# Sheet1.net
KiCad netlist of a schematic drawn in Altium Designer
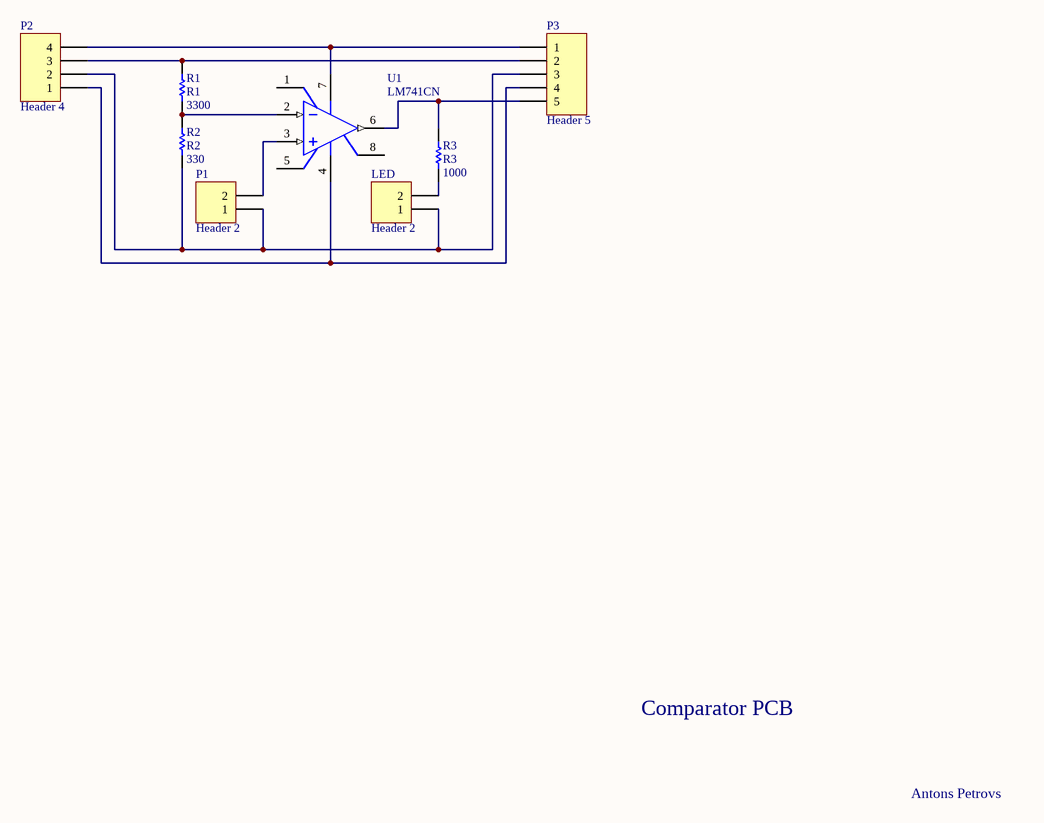
[diagram p0: Sheet1.SchDoc]

(export (version "E")
  (design (tool "Eeschema 10.0.6"))
  (components
    (comp (ref "LED")
      (value "Header 2")
      (footprint "HDR1X2")
      (description "Header, 2-Pin")
      (fields (field (name "PUBLISHER") "Altium Limited"))
      (libsource (lib "Miscellaneous Connectors") (part "Header 2"))
    )
    (comp (ref "P1")
      (value "Header 2")
      (footprint "HDR1X2")
      (description "Header, 2-Pin")
      (fields (field (name "PUBLISHER") "Altium Limited"))
      (libsource (lib "Miscellaneous Connectors") (part "Header 2"))
    )
    (comp (ref "P2")
      (value "Header 4")
      (footprint "HDR1X4")
      (description "Header, 4-Pin")
      (fields (field (name "PUBLISHER") "Altium Limited"))
      (libsource (lib "Miscellaneous Connectors") (part "Header 4"))
    )
    (comp (ref "P3")
      (value "Header 5")
      (footprint "HDR1X5")
      (description "Header, 5-Pin")
      (fields (field (name "PUBLISHER") "Altium Limited"))
      (libsource (lib "Miscellaneous Connectors") (part "Header 5"))
    )
    (comp (ref "R1")
      (value "R1")
      (footprint "AXIAL-0.3")
      (description "Resistor")
      (fields (field (name "ALTIUM_VALUE") "3300") (field (name "PUBLISHER") "Altium Limited"))
      (libsource (lib "Miscellaneous Devices") (part "Res1"))
    )
    (comp (ref "R2")
      (value "R2")
      (footprint "AXIAL-0.3")
      (description "Resistor")
      (fields (field (name "ALTIUM_VALUE") "330") (field (name "PUBLISHER") "Altium Limited"))
      (libsource (lib "Miscellaneous Devices") (part "Res1"))
    )
    (comp (ref "R3")
      (value "R3")
      (footprint "AXIAL-0.3")
      (description "Resistor")
      (fields (field (name "ALTIUM_VALUE") "1000") (field (name "PUBLISHER") "Altium Limited"))
      (libsource (lib "Miscellaneous Devices") (part "Res1"))
    )
    (comp (ref "U1")
      (value "LM741CN")
      (footprint "N08E")
      (description "Operational Amplifier, 8-pin MDIP")
      (fields
        (field (name "MANUFACTURER") "National Semiconductor")
        (field (name "PUBLISHER") "Altium Limited")
      )
      (libsource (lib "NSC Amplifier") (part "LM741CN"))
    )
  )
  (nets
    (net (code "1") (name "Net-(LED-Pad1)") (class "Default")
      (node (ref "LED") (pin "1") (pinfunction "1_1") (pintype "passive"))
      (node (ref "P1") (pin "1") (pinfunction "1_1") (pintype "passive"))
      (node (ref "P2") (pin "2") (pinfunction "2_2") (pintype "passive"))
      (node (ref "P3") (pin "3") (pinfunction "3_3") (pintype "passive"))
      (node (ref "R2") (pin "1") (pinfunction "1_1") (pintype "passive"))
    )
    (net (code "2") (name "Net-(LED-Pad2)") (class "Default")
      (node (ref "LED") (pin "2") (pinfunction "2_2") (pintype "passive"))
      (node (ref "R3") (pin "1") (pinfunction "1_1") (pintype "passive"))
    )
    (net (code "3") (name "Net-(P2-Pad3)") (class "Default")
      (node (ref "P2") (pin "3") (pinfunction "3_3") (pintype "passive"))
      (node (ref "P3") (pin "2") (pinfunction "2_2") (pintype "passive"))
      (node (ref "R1") (pin "2") (pinfunction "2_2") (pintype "passive"))
    )
    (net (code "4") (name "Net-(U1-IN+)") (class "Default")
      (node (ref "P1") (pin "2") (pinfunction "2_2") (pintype "passive"))
      (node (ref "U1") (pin "3") (pinfunction "IN+_3") (pintype "input"))
    )
    (net (code "5") (name "Net-(U1-IN-)") (class "Default")
      (node (ref "R1") (pin "1") (pinfunction "1_1") (pintype "passive"))
      (node (ref "R2") (pin "2") (pinfunction "2_2") (pintype "passive"))
      (node (ref "U1") (pin "2") (pinfunction "IN-_2") (pintype "input"))
    )
    (net (code "6") (name "Net-(U1-OUT)") (class "Default")
      (node (ref "P3") (pin "5") (pinfunction "5_5") (pintype "passive"))
      (node (ref "R3") (pin "2") (pinfunction "2_2") (pintype "passive"))
      (node (ref "U1") (pin "6") (pinfunction "OUT_6") (pintype "output"))
    )
    (net (code "7") (name "Net-(U1-V+)") (class "Default")
      (node (ref "P2") (pin "4") (pinfunction "4_4") (pintype "passive"))
      (node (ref "P3") (pin "1") (pinfunction "1_1") (pintype "passive"))
      (node (ref "U1") (pin "7") (pinfunction "V+_7") (pintype "power_in"))
    )
    (net (code "8") (name "Net-(U1-V-)") (class "Default")
      (node (ref "P2") (pin "1") (pinfunction "1_1") (pintype "passive"))
      (node (ref "P3") (pin "4") (pinfunction "4_4") (pintype "passive"))
      (node (ref "U1") (pin "4") (pinfunction "V-_4") (pintype "power_in"))
    )
    (net (code "9") (name "unconnected-(U1-NC-Pad8)") (class "Default")
      (node (ref "U1") (pin "8") (pinfunction "NC_8") (pintype "passive"))
    )
    (net (code "10") (name "unconnected-(U1-OFS_NULL-Pad1)") (class "Default")
      (node (ref "U1") (pin "1") (pinfunction "OFS_NULL_1") (pintype "passive"))
    )
    (net (code "11") (name "unconnected-(U1-OFS_NULL-Pad5)") (class "Default")
      (node (ref "U1") (pin "5") (pinfunction "OFS_NULL_5") (pintype "passive"))
    )
  )
)
